# Set-Mile-PPG-Module.net
KiCad netlist of a schematic drawn in EAGLE
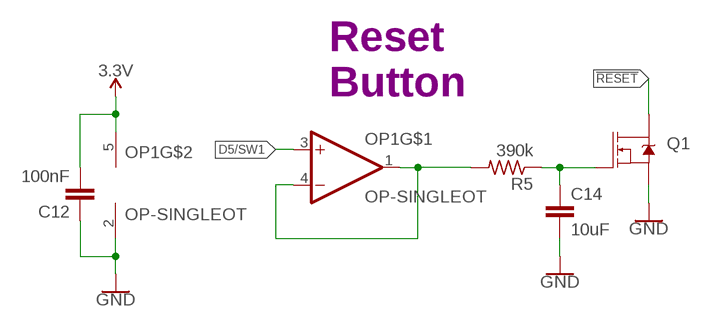
[diagram p0: schematic, sheet 1]

(export (version "E")
  (design (tool "Eeschema 10.0.6"))
  (components
    (comp (ref "C12")
      (value "100nF")
      (footprint "eagle-import:C0603")
      (libsource (lib "eagle-import") (part "CAPACITOR0603"))
    )
    (comp (ref "C14")
      (value "10uF")
      (footprint "eagle-import:C0805")
      (libsource (lib "eagle-import") (part "CAPACITOR0805"))
    )
    (comp (ref "OP1")
      (value "OP-SINGLEOT")
      (footprint "eagle-import:SOT23-5")
      (libsource (lib "eagle-import") (part "OP-SINGLEOT"))
    )
    (comp (ref "Q1")
      (value "5.8A/30V/35mΩ")
      (footprint "eagle-import:SOT23-3")
      (libsource (lib "eagle-import") (part "NFET-AO3404A"))
    )
    (comp (ref "R5")
      (value "390k")
      (footprint "eagle-import:R0603")
      (libsource (lib "eagle-import") (part "RESISTOR0603"))
    )
  )
  (nets
    (net (code "1") (name "/~{RESET}") (class "Default")
      (node (ref "Q1") (pin "3") (pinfunction "D_3") (pintype "bidirectional"))
    )
    (net (code "2") (name "3.3V") (class "Default")
      (node (ref "C12") (pin "2") (pinfunction "2_2") (pintype "passive"))
      (node (ref "OP1") (pin "5") (pinfunction "V+_5") (pintype "power_in"))
    )
    (net (code "3") (name "D5{slash}SW1") (class "Default")
      (node (ref "OP1") (pin "3") (pinfunction "+IN_3") (pintype "input"))
    )
    (net (code "4") (name "GND") (class "Default")
      (node (ref "C12") (pin "1") (pinfunction "1_1") (pintype "passive"))
      (node (ref "C14") (pin "2") (pinfunction "2_2") (pintype "passive"))
      (node (ref "OP1") (pin "2") (pinfunction "V-_2") (pintype "power_in"))
      (node (ref "Q1") (pin "2") (pinfunction "S_2") (pintype "bidirectional"))
    )
    (net (code "5") (name "Net-(OP1A--IN)") (class "Default")
      (node (ref "OP1") (pin "1") (pinfunction "OUT_1") (pintype "output"))
      (node (ref "OP1") (pin "4") (pinfunction "-IN_4") (pintype "input"))
      (node (ref "R5") (pin "2") (pinfunction "2_2") (pintype "passive"))
    )
    (net (code "6") (name "Net-(Q1-G)") (class "Default")
      (node (ref "C14") (pin "1") (pinfunction "1_1") (pintype "passive"))
      (node (ref "Q1") (pin "1") (pinfunction "G_1") (pintype "bidirectional"))
      (node (ref "R5") (pin "1") (pinfunction "1_1") (pintype "passive"))
    )
  )
)
